# baseboard.net
KiCad netlist of a schematic drawn in EAGLE
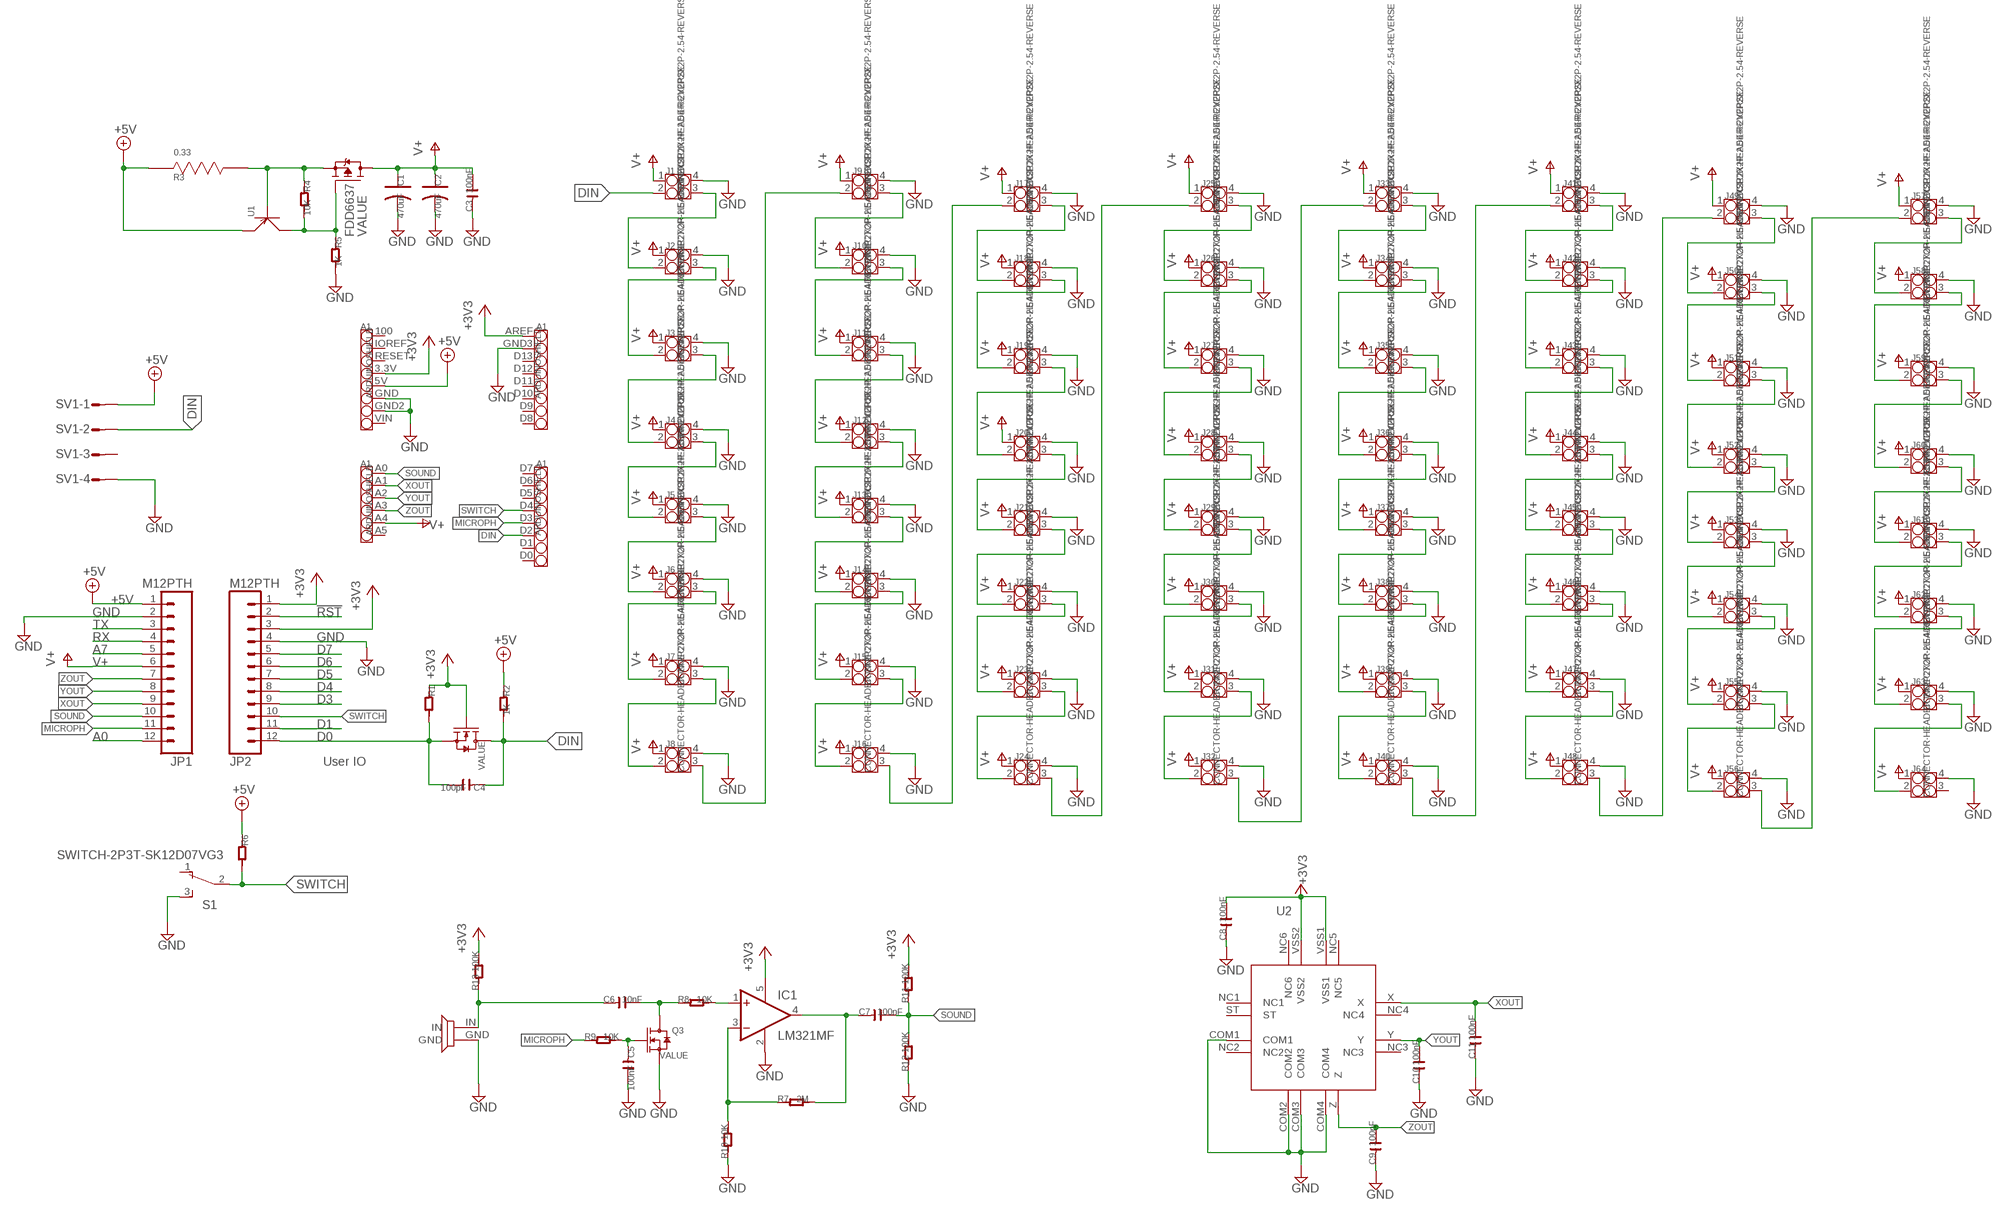
[diagram p0: schematic, sheet 1]

(export (version "E")
  (design (tool "Eeschema 10.0.6"))
  (components
    (comp (ref "2N7002")
      (value "MOSFET-N-044020001")
      (footprint "eagle-import:SOT23")
      (libsource (lib "eagle-import") (part "MOSFET-N-044020001"))
    )
    (comp (ref "A1")
      (value "ARDUINOSHIELD")
      (footprint "eagle-import:ARDUINOSHIELD")
      (libsource (lib "eagle-import") (part "ARDUINOSHIELD"))
    )
    (comp (ref "C1")
      (value "470uF")
      (footprint "eagle-import:CAPACITOR-E5-8.5")
      (libsource (lib "eagle-import") (part "C-POLARCAPACITOR-E5-8.5"))
    )
    (comp (ref "C2")
      (value "470uF")
      (footprint "eagle-import:CAPACITOR-E5-8.5")
      (libsource (lib "eagle-import") (part "C-POLARCAPACITOR-E5-8.5"))
    )
    (comp (ref "C3")
      (value "100nF")
      (footprint "eagle-import:C0603")
      (libsource (lib "eagle-import") (part "C-0603"))
    )
    (comp (ref "C4")
      (value "100pF")
      (footprint "eagle-import:C0603")
      (libsource (lib "eagle-import") (part "C-0603"))
    )
    (comp (ref "C5")
      (value "100nF")
      (footprint "eagle-import:C0603")
      (libsource (lib "eagle-import") (part "C-0603"))
    )
    (comp (ref "C6")
      (value "10nF")
      (footprint "eagle-import:C0603")
      (libsource (lib "eagle-import") (part "C-0603"))
    )
    (comp (ref "C7")
      (value "100nF")
      (footprint "eagle-import:C0603")
      (libsource (lib "eagle-import") (part "C-0603"))
    )
    (comp (ref "C8")
      (value "100nF")
      (footprint "eagle-import:C0603")
      (libsource (lib "eagle-import") (part "C-0603"))
    )
    (comp (ref "C9")
      (value "100nF")
      (footprint "eagle-import:C0603")
      (libsource (lib "eagle-import") (part "C-0603"))
    )
    (comp (ref "C10")
      (value "100nF")
      (footprint "eagle-import:C0603")
      (libsource (lib "eagle-import") (part "C-0603"))
    )
    (comp (ref "C11")
      (value "100nF")
      (footprint "eagle-import:C0603")
      (libsource (lib "eagle-import") (part "C-0603"))
    )
    (comp (ref "FDD6637")
      (value "FDD4141TO252")
      (footprint "eagle-import:TO252")
      (libsource (lib "eagle-import") (part "FDD4141TO252"))
    )
    (comp (ref "IC1")
      (value "LM321MF")
      (footprint "eagle-import:SOT23-5")
      (libsource (lib "eagle-import") (part "LM321?MF"))
    )
    (comp (ref "J1")
      (value "CONNECTOR-HEADER-2X2P2X2P-2.54-REVERSE")
      (footprint "eagle-import:2X2P-2.54-REVERSE")
      (libsource (lib "eagle-import") (part "CONNECTOR-HEADER-2X2P2X2P-2.54-REVERSE"))
    )
    (comp (ref "J2")
      (value "CONNECTOR-HEADER-2X2P2X2P-2.54-REVERSE")
      (footprint "eagle-import:2X2P-2.54-REVERSE")
      (libsource (lib "eagle-import") (part "CONNECTOR-HEADER-2X2P2X2P-2.54-REVERSE"))
    )
    (comp (ref "J3")
      (value "CONNECTOR-HEADER-2X2P2X2P-2.54-REVERSE")
      (footprint "eagle-import:2X2P-2.54-REVERSE")
      (libsource (lib "eagle-import") (part "CONNECTOR-HEADER-2X2P2X2P-2.54-REVERSE"))
    )
    (comp (ref "J4")
      (value "CONNECTOR-HEADER-2X2P2X2P-2.54-REVERSE")
      (footprint "eagle-import:2X2P-2.54-REVERSE")
      (libsource (lib "eagle-import") (part "CONNECTOR-HEADER-2X2P2X2P-2.54-REVERSE"))
    )
    (comp (ref "J5")
      (value "CONNECTOR-HEADER-2X2P2X2P-2.54-REVERSE")
      (footprint "eagle-import:2X2P-2.54-REVERSE")
      (libsource (lib "eagle-import") (part "CONNECTOR-HEADER-2X2P2X2P-2.54-REVERSE"))
    )
    (comp (ref "J6")
      (value "CONNECTOR-HEADER-2X2P2X2P-2.54-REVERSE")
      (footprint "eagle-import:2X2P-2.54-REVERSE")
      (libsource (lib "eagle-import") (part "CONNECTOR-HEADER-2X2P2X2P-2.54-REVERSE"))
    )
    (comp (ref "J7")
      (value "CONNECTOR-HEADER-2X2P2X2P-2.54-REVERSE")
      (footprint "eagle-import:2X2P-2.54-REVERSE")
      (libsource (lib "eagle-import") (part "CONNECTOR-HEADER-2X2P2X2P-2.54-REVERSE"))
    )
    (comp (ref "J8")
      (value "CONNECTOR-HEADER-2X2P2X2P-2.54-REVERSE")
      (footprint "eagle-import:2X2P-2.54-REVERSE")
      (libsource (lib "eagle-import") (part "CONNECTOR-HEADER-2X2P2X2P-2.54-REVERSE"))
    )
    (comp (ref "J9")
      (value "CONNECTOR-HEADER-2X2P2X2P-2.54-REVERSE")
      (footprint "eagle-import:2X2P-2.54-REVERSE")
      (libsource (lib "eagle-import") (part "CONNECTOR-HEADER-2X2P2X2P-2.54-REVERSE"))
    )
    (comp (ref "J10")
      (value "CONNECTOR-HEADER-2X2P2X2P-2.54-REVERSE")
      (footprint "eagle-import:2X2P-2.54-REVERSE")
      (libsource (lib "eagle-import") (part "CONNECTOR-HEADER-2X2P2X2P-2.54-REVERSE"))
    )
    (comp (ref "J11")
      (value "CONNECTOR-HEADER-2X2P2X2P-2.54-REVERSE")
      (footprint "eagle-import:2X2P-2.54-REVERSE")
      (libsource (lib "eagle-import") (part "CONNECTOR-HEADER-2X2P2X2P-2.54-REVERSE"))
    )
    (comp (ref "J12")
      (value "CONNECTOR-HEADER-2X2P2X2P-2.54-REVERSE")
      (footprint "eagle-import:2X2P-2.54-REVERSE")
      (libsource (lib "eagle-import") (part "CONNECTOR-HEADER-2X2P2X2P-2.54-REVERSE"))
    )
    (comp (ref "J13")
      (value "CONNECTOR-HEADER-2X2P2X2P-2.54-REVERSE")
      (footprint "eagle-import:2X2P-2.54-REVERSE")
      (libsource (lib "eagle-import") (part "CONNECTOR-HEADER-2X2P2X2P-2.54-REVERSE"))
    )
    (comp (ref "J14")
      (value "CONNECTOR-HEADER-2X2P2X2P-2.54-REVERSE")
      (footprint "eagle-import:2X2P-2.54-REVERSE")
      (libsource (lib "eagle-import") (part "CONNECTOR-HEADER-2X2P2X2P-2.54-REVERSE"))
    )
    (comp (ref "J15")
      (value "CONNECTOR-HEADER-2X2P2X2P-2.54-REVERSE")
      (footprint "eagle-import:2X2P-2.54-REVERSE")
      (libsource (lib "eagle-import") (part "CONNECTOR-HEADER-2X2P2X2P-2.54-REVERSE"))
    )
    (comp (ref "J16")
      (value "CONNECTOR-HEADER-2X2P2X2P-2.54-REVERSE")
      (footprint "eagle-import:2X2P-2.54-REVERSE")
      (libsource (lib "eagle-import") (part "CONNECTOR-HEADER-2X2P2X2P-2.54-REVERSE"))
    )
    (comp (ref "J17")
      (value "CONNECTOR-HEADER-2X2P2X2P-2.54-REVERSE")
      (footprint "eagle-import:2X2P-2.54-REVERSE")
      (libsource (lib "eagle-import") (part "CONNECTOR-HEADER-2X2P2X2P-2.54-REVERSE"))
    )
    (comp (ref "J18")
      (value "CONNECTOR-HEADER-2X2P2X2P-2.54-REVERSE")
      (footprint "eagle-import:2X2P-2.54-REVERSE")
      (libsource (lib "eagle-import") (part "CONNECTOR-HEADER-2X2P2X2P-2.54-REVERSE"))
    )
    (comp (ref "J19")
      (value "CONNECTOR-HEADER-2X2P2X2P-2.54-REVERSE")
      (footprint "eagle-import:2X2P-2.54-REVERSE")
      (libsource (lib "eagle-import") (part "CONNECTOR-HEADER-2X2P2X2P-2.54-REVERSE"))
    )
    (comp (ref "J20")
      (value "CONNECTOR-HEADER-2X2P2X2P-2.54-REVERSE")
      (footprint "eagle-import:2X2P-2.54-REVERSE")
      (libsource (lib "eagle-import") (part "CONNECTOR-HEADER-2X2P2X2P-2.54-REVERSE"))
    )
    (comp (ref "J21")
      (value "CONNECTOR-HEADER-2X2P2X2P-2.54-REVERSE")
      (footprint "eagle-import:2X2P-2.54-REVERSE")
      (libsource (lib "eagle-import") (part "CONNECTOR-HEADER-2X2P2X2P-2.54-REVERSE"))
    )
    (comp (ref "J22")
      (value "CONNECTOR-HEADER-2X2P2X2P-2.54-REVERSE")
      (footprint "eagle-import:2X2P-2.54-REVERSE")
      (libsource (lib "eagle-import") (part "CONNECTOR-HEADER-2X2P2X2P-2.54-REVERSE"))
    )
    (comp (ref "J23")
      (value "CONNECTOR-HEADER-2X2P2X2P-2.54-REVERSE")
      (footprint "eagle-import:2X2P-2.54-REVERSE")
      (libsource (lib "eagle-import") (part "CONNECTOR-HEADER-2X2P2X2P-2.54-REVERSE"))
    )
    (comp (ref "J24")
      (value "CONNECTOR-HEADER-2X2P2X2P-2.54-REVERSE")
      (footprint "eagle-import:2X2P-2.54-REVERSE")
      (libsource (lib "eagle-import") (part "CONNECTOR-HEADER-2X2P2X2P-2.54-REVERSE"))
    )
    (comp (ref "J25")
      (value "CONNECTOR-HEADER-2X2P2X2P-2.54-REVERSE")
      (footprint "eagle-import:2X2P-2.54-REVERSE")
      (libsource (lib "eagle-import") (part "CONNECTOR-HEADER-2X2P2X2P-2.54-REVERSE"))
    )
    (comp (ref "J26")
      (value "CONNECTOR-HEADER-2X2P2X2P-2.54-REVERSE")
      (footprint "eagle-import:2X2P-2.54-REVERSE")
      (libsource (lib "eagle-import") (part "CONNECTOR-HEADER-2X2P2X2P-2.54-REVERSE"))
    )
    (comp (ref "J27")
      (value "CONNECTOR-HEADER-2X2P2X2P-2.54-REVERSE")
      (footprint "eagle-import:2X2P-2.54-REVERSE")
      (libsource (lib "eagle-import") (part "CONNECTOR-HEADER-2X2P2X2P-2.54-REVERSE"))
    )
    (comp (ref "J28")
      (value "CONNECTOR-HEADER-2X2P2X2P-2.54-REVERSE")
      (footprint "eagle-import:2X2P-2.54-REVERSE")
      (libsource (lib "eagle-import") (part "CONNECTOR-HEADER-2X2P2X2P-2.54-REVERSE"))
    )
    (comp (ref "J29")
      (value "CONNECTOR-HEADER-2X2P2X2P-2.54-REVERSE")
      (footprint "eagle-import:2X2P-2.54-REVERSE")
      (libsource (lib "eagle-import") (part "CONNECTOR-HEADER-2X2P2X2P-2.54-REVERSE"))
    )
    (comp (ref "J30")
      (value "CONNECTOR-HEADER-2X2P2X2P-2.54-REVERSE")
      (footprint "eagle-import:2X2P-2.54-REVERSE")
      (libsource (lib "eagle-import") (part "CONNECTOR-HEADER-2X2P2X2P-2.54-REVERSE"))
    )
    (comp (ref "J31")
      (value "CONNECTOR-HEADER-2X2P2X2P-2.54-REVERSE")
      (footprint "eagle-import:2X2P-2.54-REVERSE")
      (libsource (lib "eagle-import") (part "CONNECTOR-HEADER-2X2P2X2P-2.54-REVERSE"))
    )
    (comp (ref "J32")
      (value "CONNECTOR-HEADER-2X2P2X2P-2.54-REVERSE")
      (footprint "eagle-import:2X2P-2.54-REVERSE")
      (libsource (lib "eagle-import") (part "CONNECTOR-HEADER-2X2P2X2P-2.54-REVERSE"))
    )
    (comp (ref "J33")
      (value "CONNECTOR-HEADER-2X2P2X2P-2.54-REVERSE")
      (footprint "eagle-import:2X2P-2.54-REVERSE")
      (libsource (lib "eagle-import") (part "CONNECTOR-HEADER-2X2P2X2P-2.54-REVERSE"))
    )
    (comp (ref "J34")
      (value "CONNECTOR-HEADER-2X2P2X2P-2.54-REVERSE")
      (footprint "eagle-import:2X2P-2.54-REVERSE")
      (libsource (lib "eagle-import") (part "CONNECTOR-HEADER-2X2P2X2P-2.54-REVERSE"))
    )
    (comp (ref "J35")
      (value "CONNECTOR-HEADER-2X2P2X2P-2.54-REVERSE")
      (footprint "eagle-import:2X2P-2.54-REVERSE")
      (libsource (lib "eagle-import") (part "CONNECTOR-HEADER-2X2P2X2P-2.54-REVERSE"))
    )
    (comp (ref "J36")
      (value "CONNECTOR-HEADER-2X2P2X2P-2.54-REVERSE")
      (footprint "eagle-import:2X2P-2.54-REVERSE")
      (libsource (lib "eagle-import") (part "CONNECTOR-HEADER-2X2P2X2P-2.54-REVERSE"))
    )
    (comp (ref "J37")
      (value "CONNECTOR-HEADER-2X2P2X2P-2.54-REVERSE")
      (footprint "eagle-import:2X2P-2.54-REVERSE")
      (libsource (lib "eagle-import") (part "CONNECTOR-HEADER-2X2P2X2P-2.54-REVERSE"))
    )
    (comp (ref "J38")
      (value "CONNECTOR-HEADER-2X2P2X2P-2.54-REVERSE")
      (footprint "eagle-import:2X2P-2.54-REVERSE")
      (libsource (lib "eagle-import") (part "CONNECTOR-HEADER-2X2P2X2P-2.54-REVERSE"))
    )
    (comp (ref "J39")
      (value "CONNECTOR-HEADER-2X2P2X2P-2.54-REVERSE")
      (footprint "eagle-import:2X2P-2.54-REVERSE")
      (libsource (lib "eagle-import") (part "CONNECTOR-HEADER-2X2P2X2P-2.54-REVERSE"))
    )
    (comp (ref "J40")
      (value "CONNECTOR-HEADER-2X2P2X2P-2.54-REVERSE")
      (footprint "eagle-import:2X2P-2.54-REVERSE")
      (libsource (lib "eagle-import") (part "CONNECTOR-HEADER-2X2P2X2P-2.54-REVERSE"))
    )
    (comp (ref "J41")
      (value "CONNECTOR-HEADER-2X2P2X2P-2.54-REVERSE")
      (footprint "eagle-import:2X2P-2.54-REVERSE")
      (libsource (lib "eagle-import") (part "CONNECTOR-HEADER-2X2P2X2P-2.54-REVERSE"))
    )
    (comp (ref "J42")
      (value "CONNECTOR-HEADER-2X2P2X2P-2.54-REVERSE")
      (footprint "eagle-import:2X2P-2.54-REVERSE")
      (libsource (lib "eagle-import") (part "CONNECTOR-HEADER-2X2P2X2P-2.54-REVERSE"))
    )
    (comp (ref "J43")
      (value "CONNECTOR-HEADER-2X2P2X2P-2.54-REVERSE")
      (footprint "eagle-import:2X2P-2.54-REVERSE")
      (libsource (lib "eagle-import") (part "CONNECTOR-HEADER-2X2P2X2P-2.54-REVERSE"))
    )
    (comp (ref "J44")
      (value "CONNECTOR-HEADER-2X2P2X2P-2.54-REVERSE")
      (footprint "eagle-import:2X2P-2.54-REVERSE")
      (libsource (lib "eagle-import") (part "CONNECTOR-HEADER-2X2P2X2P-2.54-REVERSE"))
    )
    (comp (ref "J45")
      (value "CONNECTOR-HEADER-2X2P2X2P-2.54-REVERSE")
      (footprint "eagle-import:2X2P-2.54-REVERSE")
      (libsource (lib "eagle-import") (part "CONNECTOR-HEADER-2X2P2X2P-2.54-REVERSE"))
    )
    (comp (ref "J46")
      (value "CONNECTOR-HEADER-2X2P2X2P-2.54-REVERSE")
      (footprint "eagle-import:2X2P-2.54-REVERSE")
      (libsource (lib "eagle-import") (part "CONNECTOR-HEADER-2X2P2X2P-2.54-REVERSE"))
    )
    (comp (ref "J47")
      (value "CONNECTOR-HEADER-2X2P2X2P-2.54-REVERSE")
      (footprint "eagle-import:2X2P-2.54-REVERSE")
      (libsource (lib "eagle-import") (part "CONNECTOR-HEADER-2X2P2X2P-2.54-REVERSE"))
    )
    (comp (ref "J48")
      (value "CONNECTOR-HEADER-2X2P2X2P-2.54-REVERSE")
      (footprint "eagle-import:2X2P-2.54-REVERSE")
      (libsource (lib "eagle-import") (part "CONNECTOR-HEADER-2X2P2X2P-2.54-REVERSE"))
    )
    (comp (ref "J49")
      (value "CONNECTOR-HEADER-2X2P2X2P-2.54-REVERSE")
      (footprint "eagle-import:2X2P-2.54-REVERSE")
      (libsource (lib "eagle-import") (part "CONNECTOR-HEADER-2X2P2X2P-2.54-REVERSE"))
    )
    (comp (ref "J50")
      (value "CONNECTOR-HEADER-2X2P2X2P-2.54-REVERSE")
      (footprint "eagle-import:2X2P-2.54-REVERSE")
      (libsource (lib "eagle-import") (part "CONNECTOR-HEADER-2X2P2X2P-2.54-REVERSE"))
    )
    (comp (ref "J51")
      (value "CONNECTOR-HEADER-2X2P2X2P-2.54-REVERSE")
      (footprint "eagle-import:2X2P-2.54-REVERSE")
      (libsource (lib "eagle-import") (part "CONNECTOR-HEADER-2X2P2X2P-2.54-REVERSE"))
    )
    (comp (ref "J52")
      (value "CONNECTOR-HEADER-2X2P2X2P-2.54-REVERSE")
      (footprint "eagle-import:2X2P-2.54-REVERSE")
      (libsource (lib "eagle-import") (part "CONNECTOR-HEADER-2X2P2X2P-2.54-REVERSE"))
    )
    (comp (ref "J53")
      (value "CONNECTOR-HEADER-2X2P2X2P-2.54-REVERSE")
      (footprint "eagle-import:2X2P-2.54-REVERSE")
      (libsource (lib "eagle-import") (part "CONNECTOR-HEADER-2X2P2X2P-2.54-REVERSE"))
    )
    (comp (ref "J54")
      (value "CONNECTOR-HEADER-2X2P2X2P-2.54-REVERSE")
      (footprint "eagle-import:2X2P-2.54-REVERSE")
      (libsource (lib "eagle-import") (part "CONNECTOR-HEADER-2X2P2X2P-2.54-REVERSE"))
    )
    (comp (ref "J55")
      (value "CONNECTOR-HEADER-2X2P2X2P-2.54-REVERSE")
      (footprint "eagle-import:2X2P-2.54-REVERSE")
      (libsource (lib "eagle-import") (part "CONNECTOR-HEADER-2X2P2X2P-2.54-REVERSE"))
    )
    (comp (ref "J56")
      (value "CONNECTOR-HEADER-2X2P2X2P-2.54-REVERSE")
      (footprint "eagle-import:2X2P-2.54-REVERSE")
      (libsource (lib "eagle-import") (part "CONNECTOR-HEADER-2X2P2X2P-2.54-REVERSE"))
    )
    (comp (ref "J57")
      (value "CONNECTOR-HEADER-2X2P2X2P-2.54-REVERSE")
      (footprint "eagle-import:2X2P-2.54-REVERSE")
      (libsource (lib "eagle-import") (part "CONNECTOR-HEADER-2X2P2X2P-2.54-REVERSE"))
    )
    (comp (ref "J58")
      (value "CONNECTOR-HEADER-2X2P2X2P-2.54-REVERSE")
      (footprint "eagle-import:2X2P-2.54-REVERSE")
      (libsource (lib "eagle-import") (part "CONNECTOR-HEADER-2X2P2X2P-2.54-REVERSE"))
    )
    (comp (ref "J59")
      (value "CONNECTOR-HEADER-2X2P2X2P-2.54-REVERSE")
      (footprint "eagle-import:2X2P-2.54-REVERSE")
      (libsource (lib "eagle-import") (part "CONNECTOR-HEADER-2X2P2X2P-2.54-REVERSE"))
    )
    (comp (ref "J60")
      (value "CONNECTOR-HEADER-2X2P2X2P-2.54-REVERSE")
      (footprint "eagle-import:2X2P-2.54-REVERSE")
      (libsource (lib "eagle-import") (part "CONNECTOR-HEADER-2X2P2X2P-2.54-REVERSE"))
    )
    (comp (ref "J61")
      (value "CONNECTOR-HEADER-2X2P2X2P-2.54-REVERSE")
      (footprint "eagle-import:2X2P-2.54-REVERSE")
      (libsource (lib "eagle-import") (part "CONNECTOR-HEADER-2X2P2X2P-2.54-REVERSE"))
    )
    (comp (ref "J62")
      (value "CONNECTOR-HEADER-2X2P2X2P-2.54-REVERSE")
      (footprint "eagle-import:2X2P-2.54-REVERSE")
      (libsource (lib "eagle-import") (part "CONNECTOR-HEADER-2X2P2X2P-2.54-REVERSE"))
    )
    (comp (ref "J63")
      (value "CONNECTOR-HEADER-2X2P2X2P-2.54-REVERSE")
      (footprint "eagle-import:2X2P-2.54-REVERSE")
      (libsource (lib "eagle-import") (part "CONNECTOR-HEADER-2X2P2X2P-2.54-REVERSE"))
    )
    (comp (ref "J64")
      (value "CONNECTOR-HEADER-2X2P2X2P-2.54-REVERSE")
      (footprint "eagle-import:2X2P-2.54-REVERSE")
      (libsource (lib "eagle-import") (part "CONNECTOR-HEADER-2X2P2X2P-2.54-REVERSE"))
    )
    (comp (ref "JP1")
      (value "M12PTH")
      (footprint "eagle-import:1X12-SMALL-PADS")
      (libsource (lib "eagle-import") (part "M12PTH"))
    )
    (comp (ref "JP2")
      (value "M12PTH")
      (footprint "eagle-import:1X12-SMALL-PADS")
      (libsource (lib "eagle-import") (part "M12PTH"))
    )
    (comp (ref "Q3")
      (value "MOSFET-N-044020001")
      (footprint "eagle-import:SOT23")
      (libsource (lib "eagle-import") (part "MOSFET-N-044020001"))
    )
    (comp (ref "R1")
      (value "R-0603")
      (footprint "eagle-import:R0603")
      (libsource (lib "eagle-import") (part "R-0603"))
    )
    (comp (ref "R2")
      (value "1K")
      (footprint "eagle-import:R0603")
      (libsource (lib "eagle-import") (part "R-0603"))
    )
    (comp (ref "R3")
      (value "0.33")
      (footprint "eagle-import:RESISTOR-3W-20MM")
      (libsource (lib "eagle-import") (part "RESISTOR-3W-20MM"))
    )
    (comp (ref "R4")
      (value "10K")
      (footprint "eagle-import:R0603")
      (libsource (lib "eagle-import") (part "R-0603"))
    )
    (comp (ref "R5")
      (value "1K")
      (footprint "eagle-import:R0603")
      (libsource (lib "eagle-import") (part "R-0603"))
    )
    (comp (ref "R6")
      (value "R-0603")
      (footprint "eagle-import:R0603")
      (libsource (lib "eagle-import") (part "R-0603"))
    )
    (comp (ref "R7")
      (value "2M")
      (footprint "eagle-import:R0603")
      (libsource (lib "eagle-import") (part "R-0603"))
    )
    (comp (ref "R8")
      (value "10K")
      (footprint "eagle-import:R0603")
      (libsource (lib "eagle-import") (part "R-0603"))
    )
    (comp (ref "R9")
      (value "10K")
      (footprint "eagle-import:R0603")
      (libsource (lib "eagle-import") (part "R-0603"))
    )
    (comp (ref "R10")
      (value "10K")
      (footprint "eagle-import:R0603")
      (libsource (lib "eagle-import") (part "R-0603"))
    )
    (comp (ref "R11")
      (value "100K")
      (footprint "eagle-import:R0603")
      (libsource (lib "eagle-import") (part "R-0603"))
    )
    (comp (ref "R12")
      (value "100K")
      (footprint "eagle-import:R0603")
      (libsource (lib "eagle-import") (part "R-0603"))
    )
    (comp (ref "R13")
      (value "100K")
      (footprint "eagle-import:R0603")
      (libsource (lib "eagle-import") (part "R-0603"))
    )
    (comp (ref "S1")
      (value "SWITCH-2P3T-SK12D07VG3")
      (footprint "eagle-import:SWITCH-2P3T-SK12D07VG3")
      (libsource (lib "eagle-import") (part "SWITCH-2P3T-SK12D07VG3"))
    )
    (comp (ref "SV1")
      (value "S04P")
      (footprint "eagle-import:S04P")
      (libsource (lib "eagle-import") (part "S04P"))
    )
    (comp (ref "U$1")
      (value "MICROPHONE")
      (footprint "eagle-import:MICROPHONE")
      (libsource (lib "eagle-import") (part "MICROPHONE"))
    )
    (comp (ref "U1")
      (value "TRANSISTOR-PNP-041003001")
      (footprint "eagle-import:SOT23")
      (libsource (lib "eagle-import") (part "TRANSISTOR-PNP-041003001"))
    )
    (comp (ref "U2")
      (value "ADXL335")
      (footprint "eagle-import:ADXL335")
      (libsource (lib "eagle-import") (part "ADXL335"))
    )
  )
  (nets
    (net (code "1") (name "+3V3") (class "Default")
      (node (ref "2N7002") (pin "1") (pinfunction "G_1") (pintype "passive"))
      (node (ref "A1") (pin "3.3V") (pinfunction "3.3V_3.3V") (pintype "bidirectional"))
      (node (ref "A1") (pin "AREF") (pinfunction "AREF_AREF") (pintype "bidirectional"))
      (node (ref "C8") (pin "2") (pinfunction "2_2") (pintype "bidirectional"))
      (node (ref "IC1") (pin "5") (pinfunction "V+_5") (pintype "power_in"))
      (node (ref "JP2") (pin "1") (pinfunction "1_1") (pintype "passive"))
      (node (ref "JP2") (pin "3") (pinfunction "3_3") (pintype "passive"))
      (node (ref "R1") (pin "1") (pinfunction "1_1") (pintype "bidirectional"))
      (node (ref "R11") (pin "2") (pinfunction "2_2") (pintype "bidirectional"))
      (node (ref "R13") (pin "2") (pinfunction "2_2") (pintype "bidirectional"))
      (node (ref "U2") (pin "VSS1") (pinfunction "VSS1_VSS1") (pintype "bidirectional"))
      (node (ref "U2") (pin "VSS2") (pinfunction "VSS2_VSS2") (pintype "bidirectional"))
    )
    (net (code "2") (name "+5V") (class "Default")
      (node (ref "A1") (pin "5V") (pinfunction "5V_5V") (pintype "bidirectional"))
      (node (ref "JP1") (pin "1") (pinfunction "1_1") (pintype "passive"))
      (node (ref "R2") (pin "1") (pinfunction "1_1") (pintype "bidirectional"))
      (node (ref "R3") (pin "1") (pinfunction "1_1") (pintype "bidirectional"))
      (node (ref "R6") (pin "1") (pinfunction "1_1") (pintype "bidirectional"))
      (node (ref "SV1") (pin "1") (pinfunction "S_1") (pintype "passive"))
      (node (ref "U1") (pin "2") (pinfunction "E_2") (pintype "passive"))
    )
    (net (code "3") (name "/A0") (class "Default")
      (node (ref "JP1") (pin "12") (pinfunction "12_12") (pintype "passive"))
    )
    (net (code "4") (name "/A7") (class "Default")
      (node (ref "JP1") (pin "5") (pinfunction "5_5") (pintype "passive"))
    )
    (net (code "5") (name "/D0") (class "Default")
      (node (ref "2N7002") (pin "2") (pinfunction "S_2") (pintype "passive"))
      (node (ref "C4") (pin "2") (pinfunction "2_2") (pintype "bidirectional"))
      (node (ref "JP2") (pin "12") (pinfunction "12_12") (pintype "passive"))
      (node (ref "R1") (pin "2") (pinfunction "2_2") (pintype "bidirectional"))
    )
    (net (code "6") (name "/D1") (class "Default")
      (node (ref "JP2") (pin "11") (pinfunction "11_11") (pintype "passive"))
    )
    (net (code "7") (name "/D3") (class "Default")
      (node (ref "JP2") (pin "9") (pinfunction "9_9") (pintype "passive"))
    )
    (net (code "8") (name "/D4") (class "Default")
      (node (ref "JP2") (pin "8") (pinfunction "8_8") (pintype "passive"))
    )
    (net (code "9") (name "/D5") (class "Default")
      (node (ref "JP2") (pin "7") (pinfunction "7_7") (pintype "passive"))
    )
    (net (code "10") (name "/D6") (class "Default")
      (node (ref "JP2") (pin "6") (pinfunction "6_6") (pintype "passive"))
    )
    (net (code "11") (name "/D7") (class "Default")
      (node (ref "JP2") (pin "5") (pinfunction "5_5") (pintype "passive"))
    )
    (net (code "12") (name "/RX") (class "Default")
      (node (ref "JP1") (pin "4") (pinfunction "4_4") (pintype "passive"))
    )
    (net (code "13") (name "/TX") (class "Default")
      (node (ref "JP1") (pin "3") (pinfunction "3_3") (pintype "passive"))
    )
    (net (code "14") (name "/~{RST}") (class "Default")
      (node (ref "JP2") (pin "2") (pinfunction "2_2") (pintype "passive"))
    )
    (net (code "15") (name "DIN") (class "Default")
      (node (ref "2N7002") (pin "3") (pinfunction "D_3") (pintype "passive"))
      (node (ref "A1") (pin "D2") (pinfunction "D2_D2") (pintype "bidirectional"))
      (node (ref "C4") (pin "1") (pinfunction "1_1") (pintype "bidirectional"))
      (node (ref "J1") (pin "2") (pinfunction "2_2") (pintype "bidirectional"))
      (node (ref "R2") (pin "2") (pinfunction "2_2") (pintype "bidirectional"))
      (node (ref "SV1") (pin "2") (pinfunction "S_2") (pintype "passive"))
    )
    (net (code "16") (name "GND") (class "Default")
      (node (ref "A1") (pin "GND") (pinfunction "GND_GND") (pintype "bidirectional"))
      (node (ref "A1") (pin "GND2") (pinfunction "GND2_GND2") (pintype "bidirectional"))
      (node (ref "A1") (pin "GND3") (pinfunction "GND3_GND3") (pintype "bidirectional"))
      (node (ref "C1") (pin "-") (pinfunction "2_-") (pintype "bidirectional"))
      (node (ref "C10") (pin "1") (pinfunction "1_1") (pintype "bidirectional"))
      (node (ref "C11") (pin "1") (pinfunction "1_1") (pintype "bidirectional"))
      (node (ref "C2") (pin "-") (pinfunction "2_-") (pintype "bidirectional"))
      (node (ref "C3") (pin "1") (pinfunction "1_1") (pintype "bidirectional"))
      (node (ref "C5") (pin "2") (pinfunction "2_2") (pintype "bidirectional"))
      (node (ref "C8") (pin "1") (pinfunction "1_1") (pintype "bidirectional"))
      (node (ref "C9") (pin "1") (pinfunction "1_1") (pintype "bidirectional"))
      (node (ref "IC1") (pin "2") (pinfunction "V-_2") (pintype "power_in"))
      (node (ref "J1") (pin "4") (pinfunction "4_4") (pintype "bidirectional"))
      (node (ref "J10") (pin "4") (pinfunction "4_4") (pintype "bidirectional"))
      (node (ref "J11") (pin "4") (pinfunction "4_4") (pintype "bidirectional"))
      (node (ref "J12") (pin "4") (pinfunction "4_4") (pintype "bidirectional"))
      (node (ref "J13") (pin "4") (pinfunction "4_4") (pintype "bidirectional"))
      (node (ref "J14") (pin "4") (pinfunction "4_4") (pintype "bidirectional"))
      (node (ref "J15") (pin "4") (pinfunction "4_4") (pintype "bidirectional"))
      (node (ref "J16") (pin "4") (pinfunction "4_4") (pintype "bidirectional"))
      (node (ref "J17") (pin "4") (pinfunction "4_4") (pintype "bidirectional"))
      (node (ref "J18") (pin "4") (pinfunction "4_4") (pintype "bidirectional"))
      (node (ref "J19") (pin "4") (pinfunction "4_4") (pintype "bidirectional"))
      (node (ref "J2") (pin "4") (pinfunction "4_4") (pintype "bidirectional"))
      (node (ref "J20") (pin "4") (pinfunction "4_4") (pintype "bidirectional"))
      (node (ref "J21") (pin "4") (pinfunction "4_4") (pintype "bidirectional"))
      (node (ref "J22") (pin "4") (pinfunction "4_4") (pintype "bidirectional"))
      (node (ref "J23") (pin "4") (pinfunction "4_4") (pintype "bidirectional"))
      (node (ref "J24") (pin "4") (pinfunction "4_4") (pintype "bidirectional"))
      (node (ref "J25") (pin "4") (pinfunction "4_4") (pintype "bidirectional"))
      (node (ref "J26") (pin "4") (pinfunction "4_4") (pintype "bidirectional"))
      (node (ref "J27") (pin "4") (pinfunction "4_4") (pintype "bidirectional"))
      (node (ref "J28") (pin "4") (pinfunction "4_4") (pintype "bidirectional"))
      (node (ref "J29") (pin "4") (pinfunction "4_4") (pintype "bidirectional"))
      (node (ref "J3") (pin "4") (pinfunction "4_4") (pintype "bidirectional"))
      (node (ref "J30") (pin "4") (pinfunction "4_4") (pintype "bidirectional"))
      (node (ref "J31") (pin "4") (pinfunction "4_4") (pintype "bidirectional"))
      (node (ref "J32") (pin "4") (pinfunction "4_4") (pintype "bidirectional"))
      (node (ref "J33") (pin "4") (pinfunction "4_4") (pintype "bidirectional"))
      (node (ref "J34") (pin "4") (pinfunction "4_4") (pintype "bidirectional"))
      (node (ref "J35") (pin "4") (pinfunction "4_4") (pintype "bidirectional"))
      (node (ref "J36") (pin "4") (pinfunction "4_4") (pintype "bidirectional"))
      (node (ref "J37") (pin "4") (pinfunction "4_4") (pintype "bidirectional"))
      (node (ref "J38") (pin "4") (pinfunction "4_4") (pintype "bidirectional"))
      (node (ref "J39") (pin "4") (pinfunction "4_4") (pintype "bidirectional"))
      (node (ref "J4") (pin "4") (pinfunction "4_4") (pintype "bidirectional"))
      (node (ref "J40") (pin "4") (pinfunction "4_4") (pintype "bidirectional"))
      (node (ref "J41") (pin "4") (pinfunction "4_4") (pintype "bidirectional"))
      (node (ref "J42") (pin "4") (pinfunction "4_4") (pintype "bidirectional"))
      (node (ref "J43") (pin "4") (pinfunction "4_4") (pintype "bidirectional"))
      (node (ref "J44") (pin "4") (pinfunction "4_4") (pintype "bidirectional"))
      (node (ref "J45") (pin "4") (pinfunction "4_4") (pintype "bidirectional"))
      (node (ref "J46") (pin "4") (pinfunction "4_4") (pintype "bidirectional"))
      (node (ref "J47") (pin "4") (pinfunction "4_4") (pintype "bidirectional"))
      (node (ref "J48") (pin "4") (pinfunction "4_4") (pintype "bidirectional"))
      (node (ref "J49") (pin "4") (pinfunction "4_4") (pintype "bidirectional"))
      (node (ref "J5") (pin "4") (pinfunction "4_4") (pintype "bidirectional"))
      (node (ref "J50") (pin "4") (pinfunction "4_4") (pintype "bidirectional"))
      (node (ref "J51") (pin "4") (pinfunction "4_4") (pintype "bidirectional"))
      (node (ref "J52") (pin "4") (pinfunction "4_4") (pintype "bidirectional"))
      (node (ref "J53") (pin "4") (pinfunction "4_4") (pintype "bidirectional"))
      (node (ref "J54") (pin "4") (pinfunction "4_4") (pintype "bidirectional"))
      (node (ref "J55") (pin "4") (pinfunction "4_4") (pintype "bidirectional"))
      (node (ref "J56") (pin "4") (pinfunction "4_4") (pintype "bidirectional"))
      (node (ref "J57") (pin "4") (pinfunction "4_4") (pintype "bidirectional"))
      (node (ref "J58") (pin "4") (pinfunction "4_4") (pintype "bidirectional"))
      (node (ref "J59") (pin "4") (pinfunction "4_4") (pintype "bidirectional"))
      (node (ref "J6") (pin "4") (pinfunction "4_4") (pintype "bidirectional"))
      (node (ref "J60") (pin "4") (pinfunction "4_4") (pintype "bidirectional"))
      (node (ref "J61") (pin "4") (pinfunction "4_4") (pintype "bidirectional"))
      (node (ref "J62") (pin "4") (pinfunction "4_4") (pintype "bidirectional"))
      (node (ref "J63") (pin "4") (pinfunction "4_4") (pintype "bidirectional"))
      (node (ref "J64") (pin "4") (pinfunction "4_4") (pintype "bidirectional"))
      (node (ref "J7") (pin "4") (pinfunction "4_4") (pintype "bidirectional"))
      (node (ref "J8") (pin "4") (pinfunction "4_4") (pintype "bidirectional"))
      (node (ref "J9") (pin "4") (pinfunction "4_4") (pintype "bidirectional"))
      (node (ref "JP1") (pin "2") (pinfunction "2_2") (pintype "passive"))
      (node (ref "JP2") (pin "4") (pinfunction "4_4") (pintype "passive"))
      (node (ref "Q3") (pin "2") (pinfunction "S_2") (pintype "passive"))
      (node (ref "R10") (pin "1") (pinfunction "1_1") (pintype "bidirectional"))
      (node (ref "R12") (pin "1") (pinfunction "1_1") (pintype "bidirectional"))
      (node (ref "R5") (pin "2") (pinfunction "2_2") (pintype "bidirectional"))
      (node (ref "S1") (pin "3") (pinfunction "S_3") (pintype "passive"))
      (node (ref "SV1") (pin "4") (pinfunction "S_4") (pintype "passive"))
      (node (ref "U$1") (pin "GND") (pinfunction "GND_GND") (pintype "bidirectional"))
      (node (ref "U2") (pin "COM1") (pinfunction "COM1_COM1") (pintype "bidirectional"))
      (node (ref "U2") (pin "COM2") (pinfunction "COM2_COM2") (pintype "bidirectional"))
      (node (ref "U2") (pin "COM3") (pinfunction "COM3_COM3") (pintype "bidirectional"))
      (node (ref "U2") (pin "COM4") (pinfunction "COM4_COM4") (pintype "bidirectional"))
    )
    (net (code "17") (name "MICROPH") (class "Default")
      (node (ref "A1") (pin "D3") (pinfunction "D3_D3") (pintype "bidirectional"))
      (node (ref "JP1") (pin "11") (pinfunction "11_11") (pintype "passive"))
      (node (ref "R9") (pin "1") (pinfunction "1_1") (pintype "bidirectional"))
    )
    (net (code "18") (name "Net-(C6-Pad1)") (class "Default")
      (node (ref "C6") (pin "1") (pinfunction "1_1") (pintype "bidirectional"))
      (node (ref "R13") (pin "1") (pinfunction "1_1") (pintype "bidirectional"))
      (node (ref "U$1") (pin "IN") (pinfunction "IN_IN") (pintype "bidirectional"))
    )
    (net (code "19") (name "Net-(FDD6637-G)") (class "Default")
      (node (ref "FDD6637") (pin "1") (pinfunction "G_1") (pintype "passive"))
      (node (ref "R4") (pin "2") (pinfunction "2_2") (pintype "bidirectional"))
      (node (ref "R5") (pin "1") (pinfunction "1_1") (pintype "bidirectional"))
      (node (ref "U1") (pin "3") (pinfunction "C_3") (pintype "passive"))
    )
    (net (code "20") (name "Net-(FDD6637-S)") (class "Default")
      (node (ref "FDD6637") (pin "2") (pinfunction "S_2") (pintype "passive"))
      (node (ref "R3") (pin "2") (pinfunction "2_2") (pintype "bidirectional"))
      (node (ref "R4") (pin "1") (pinfunction "1_1") (pintype "bidirectional"))
      (node (ref "U1") (pin "1") (pinfunction "B_1") (pintype "passive"))
    )
    (net (code "21") (name "Net-(IC1-+IN)") (class "Default")
      (node (ref "IC1") (pin "1") (pinfunction "+IN_1") (pintype "input"))
      (node (ref "R8") (pin "2") (pinfunction "2_2") (pintype "bidirectional"))
    )
    (net (code "22") (name "Net-(IC1--IN)") (class "Default")
      (node (ref "IC1") (pin "3") (pinfunction "-IN_3") (pintype "input"))
      (node (ref "R10") (pin "2") (pinfunction "2_2") (pintype "bidirectional"))
      (node (ref "R7") (pin "1") (pinfunction "1_1") (pintype "bidirectional"))
    )
    (net (code "23") (name "Net-(IC1-OUT)") (class "Default")
      (node (ref "C7") (pin "1") (pinfunction "1_1") (pintype "bidirectional"))
      (node (ref "IC1") (pin "4") (pinfunction "OUT_4") (pintype "output"))
      (node (ref "R7") (pin "2") (pinfunction "2_2") (pintype "bidirectional"))
    )
    (net (code "24") (name "Net-(J1-Pad3)") (class "Default")
      (node (ref "J1") (pin "3") (pinfunction "3_3") (pintype "bidirectional"))
      (node (ref "J2") (pin "2") (pinfunction "2_2") (pintype "bidirectional"))
    )
    (net (code "25") (name "Net-(J2-Pad3)") (class "Default")
      (node (ref "J2") (pin "3") (pinfunction "3_3") (pintype "bidirectional"))
      (node (ref "J3") (pin "2") (pinfunction "2_2") (pintype "bidirectional"))
    )
    (net (code "26") (name "Net-(J3-Pad3)") (class "Default")
      (node (ref "J3") (pin "3") (pinfunction "3_3") (pintype "bidirectional"))
      (node (ref "J4") (pin "2") (pinfunction "2_2") (pintype "bidirectional"))
    )
    (net (code "27") (name "Net-(J4-Pad3)") (class "Default")
      (node (ref "J4") (pin "3") (pinfunction "3_3") (pintype "bidirectional"))
      (node (ref "J5") (pin "2") (pinfunction "2_2") (pintype "bidirectional"))
    )
    (net (code "28") (name "Net-(J5-Pad3)") (class "Default")
      (node (ref "J5") (pin "3") (pinfunction "3_3") (pintype "bidirectional"))
      (node (ref "J6") (pin "2") (pinfunction "2_2") (pintype "bidirectional"))
    )
    (net (code "29") (name "Net-(J6-Pad3)") (class "Default")
      (node (ref "J6") (pin "3") (pinfunction "3_3") (pintype "bidirectional"))
      (node (ref "J7") (pin "2") (pinfunction "2_2") (pintype "bidirectional"))
    )
    (net (code "30") (name "Net-(J7-Pad3)") (class "Default")
      (node (ref "J7") (pin "3") (pinfunction "3_3") (pintype "bidirectional"))
      (node (ref "J8") (pin "2") (pinfunction "2_2") (pintype "bidirectional"))
    )
    (net (code "31") (name "Net-(J8-Pad3)") (class "Default")
      (node (ref "J8") (pin "3") (pinfunction "3_3") (pintype "bidirectional"))
      (node (ref "J9") (pin "2") (pinfunction "2_2") (pintype "bidirectional"))
    )
    (net (code "32") (name "Net-(J10-Pad2)") (class "Default")
      (node (ref "J10") (pin "2") (pinfunction "2_2") (pintype "bidirectional"))
      (node (ref "J9") (pin "3") (pinfunction "3_3") (pintype "bidirectional"))
    )
    (net (code "33") (name "Net-(J10-Pad3)") (class "Default")
      (node (ref "J10") (pin "3") (pinfunction "3_3") (pintype "bidirectional"))
      (node (ref "J11") (pin "2") (pinfunction "2_2") (pintype "bidirectional"))
    )
    (net (code "34") (name "Net-(J11-Pad3)") (class "Default")
      (node (ref "J11") (pin "3") (pinfunction "3_3") (pintype "bidirectional"))
      (node (ref "J12") (pin "2") (pinfunction "2_2") (pintype "bidirectional"))
    )
    (net (code "35") (name "Net-(J12-Pad3)") (class "Default")
      (node (ref "J12") (pin "3") (pinfunction "3_3") (pintype "bidirectional"))
      (node (ref "J13") (pin "2") (pinfunction "2_2") (pintype "bidirectional"))
    )
    (net (code "36") (name "Net-(J13-Pad3)") (class "Default")
      (node (ref "J13") (pin "3") (pinfunction "3_3") (pintype "bidirectional"))
      (node (ref "J14") (pin "2") (pinfunction "2_2") (pintype "bidirectional"))
    )
    (net (code "37") (name "Net-(J14-Pad3)") (class "Default")
      (node (ref "J14") (pin "3") (pinfunction "3_3") (pintype "bidirectional"))
      (node (ref "J15") (pin "2") (pinfunction "2_2") (pintype "bidirectional"))
    )
    (net (code "38") (name "Net-(J15-Pad3)") (class "Default")
      (node (ref "J15") (pin "3") (pinfunction "3_3") (pintype "bidirectional"))
      (node (ref "J16") (pin "2") (pinfunction "2_2") (pintype "bidirectional"))
    )
    (net (code "39") (name "Net-(J16-Pad3)") (class "Default")
      (node (ref "J16") (pin "3") (pinfunction "3_3") (pintype "bidirectional"))
      (node (ref "J17") (pin "2") (pinfunction "2_2") (pintype "bidirectional"))
    )
    (net (code "40") (name "Net-(J17-Pad3)") (class "Default")
      (node (ref "J17") (pin "3") (pinfunction "3_3") (pintype "bidirectional"))
      (node (ref "J18") (pin "2") (pinfunction "2_2") (pintype "bidirectional"))
    )
    (net (code "41") (name "Net-(J18-Pad3)") (class "Default")
      (node (ref "J18") (pin "3") (pinfunction "3_3") (pintype "bidirectional"))
      (node (ref "J19") (pin "2") (pinfunction "2_2") (pintype "bidirectional"))
    )
    (net (code "42") (name "Net-(J19-Pad3)") (class "Default")
      (node (ref "J19") (pin "3") (pinfunction "3_3") (pintype "bidirectional"))
      (node (ref "J20") (pin "2") (pinfunction "2_2") (pintype "bidirectional"))
    )
    (net (code "43") (name "Net-(J20-Pad3)") (class "Default")
      (node (ref "J20") (pin "3") (pinfunction "3_3") (pintype "bidirectional"))
      (node (ref "J21") (pin "2") (pinfunction "2_2") (pintype "bidirectional"))
    )
    (net (code "44") (name "Net-(J21-Pad3)") (class "Default")
      (node (ref "J21") (pin "3") (pinfunction "3_3") (pintype "bidirectional"))
      (node (ref "J22") (pin "2") (pinfunction "2_2") (pintype "bidirectional"))
    )
    (net (code "45") (name "Net-(J22-Pad3)") (class "Default")
      (node (ref "J22") (pin "3") (pinfunction "3_3") (pintype "bidirectional"))
      (node (ref "J23") (pin "2") (pinfunction "2_2") (pintype "bidirectional"))
    )
    (net (code "46") (name "Net-(J23-Pad3)") (class "Default")
      (node (ref "J23") (pin "3") (pinfunction "3_3") (pintype "bidirectional"))
      (node (ref "J24") (pin "2") (pinfunction "2_2") (pintype "bidirectional"))
    )
    (net (code "47") (name "Net-(J24-Pad3)") (class "Default")
      (node (ref "J24") (pin "3") (pinfunction "3_3") (pintype "bidirectional"))
      (node (ref "J25") (pin "2") (pinfunction "2_2") (pintype "bidirectional"))
    )
    (net (code "48") (name "Net-(J25-Pad3)") (class "Default")
      (node (ref "J25") (pin "3") (pinfunction "3_3") (pintype "bidirectional"))
      (node (ref "J26") (pin "2") (pinfunction "2_2") (pintype "bidirectional"))
    )
    (net (code "49") (name "Net-(J26-Pad3)") (class "Default")
      (node (ref "J26") (pin "3") (pinfunction "3_3") (pintype "bidirectional"))
      (node (ref "J27") (pin "2") (pinfunction "2_2") (pintype "bidirectional"))
    )
    (net (code "50") (name "Net-(J27-Pad3)") (class "Default")
      (node (ref "J27") (pin "3") (pinfunction "3_3") (pintype "bidirectional"))
      (node (ref "J28") (pin "2") (pinfunction "2_2") (pintype "bidirectional"))
    )
    (net (code "51") (name "Net-(J28-Pad3)") (class "Default")
      (node (ref "J28") (pin "3") (pinfunction "3_3") (pintype "bidirectional"))
      (node (ref "J29") (pin "2") (pinfunction "2_2") (pintype "bidirectional"))
    )
    (net (code "52") (name "Net-(J29-Pad3)") (class "Default")
      (node (ref "J29") (pin "3") (pinfunction "3_3") (pintype "bidirectional"))
      (node (ref "J30") (pin "2") (pinfunction "2_2") (pintype "bidirectional"))
    )
    (net (code "53") (name "Net-(J30-Pad3)") (class "Default")
      (node (ref "J30") (pin "3") (pinfunction "3_3") (pintype "bidirectional"))
      (node (ref "J31") (pin "2") (pinfunction "2_2") (pintype "bidirectional"))
    )
    (net (code "54") (name "Net-(J31-Pad3)") (class "Default")
      (node (ref "J31") (pin "3") (pinfunction "3_3") (pintype "bidirectional"))
      (node (ref "J32") (pin "2") (pinfunction "2_2") (pintype "bidirectional"))
    )
    (net (code "55") (name "Net-(J32-Pad3)") (class "Default")
      (node (ref "J32") (pin "3") (pinfunction "3_3") (pintype "bidirectional"))
      (node (ref "J33") (pin "2") (pinfunction "2_2") (pintype "bidirectional"))
    )
    (net (code "56") (name "Net-(J33-Pad3)") (class "Default")
      (node (ref "J33") (pin "3") (pinfunction "3_3") (pintype "bidirectional"))
      (node (ref "J34") (pin "2") (pinfunction "2_2") (pintype "bidirectional"))
    )
    (net (code "57") (name "Net-(J34-Pad3)") (class "Default")
      (node (ref "J34") (pin "3") (pinfunction "3_3") (pintype "bidirectional"))
      (node (ref "J35") (pin "2") (pinfunction "2_2") (pintype "bidirectional"))
    )
    (net (code "58") (name "Net-(J35-Pad3)") (class "Default")
      (node (ref "J35") (pin "3") (pinfunction "3_3") (pintype "bidirectional"))
      (node (ref "J36") (pin "2") (pinfunction "2_2") (pintype "bidirectional"))
    )
    (net (code "59") (name "Net-(J36-Pad3)") (class "Default")
      (node (ref "J36") (pin "3") (pinfunction "3_3") (pintype "bidirectional"))
      (node (ref "J37") (pin "2") (pinfunction "2_2") (pintype "bidirectional"))
    )
    (net (code "60") (name "Net-(J37-Pad3)") (class "Default")
      (node (ref "J37") (pin "3") (pinfunction "3_3") (pintype "bidirectional"))
      (node (ref "J38") (pin "2") (pinfunction "2_2") (pintype "bidirectional"))
    )
    (net (code "61") (name "Net-(J38-Pad3)") (class "Default")
      (node (ref "J38") (pin "3") (pinfunction "3_3") (pintype "bidirectional"))
      (node (ref "J39") (pin "2") (pinfunction "2_2") (pintype "bidirectional"))
    )
    (net (code "62") (name "Net-(J39-Pad3)") (class "Default")
      (node (ref "J39") (pin "3") (pinfunction "3_3") (pintype "bidirectional"))
      (node (ref "J40") (pin "2") (pinfunction "2_2") (pintype "bidirectional"))
    )
    (net (code "63") (name "Net-(J40-Pad3)") (class "Default")
      (node (ref "J40") (pin "3") (pinfunction "3_3") (pintype "bidirectional"))
      (node (ref "J41") (pin "2") (pinfunction "2_2") (pintype "bidirectional"))
    )
    (net (code "64") (name "Net-(J41-Pad3)") (class "Default")
      (node (ref "J41") (pin "3") (pinfunction "3_3") (pintype "bidirectional"))
      (node (ref "J42") (pin "2") (pinfunction "2_2") (pintype "bidirectional"))
    )
    (net (code "65") (name "Net-(J42-Pad3)") (class "Default")
      (node (ref "J42") (pin "3") (pinfunction "3_3") (pintype "bidirectional"))
      (node (ref "J43") (pin "2") (pinfunction "2_2") (pintype "bidirectional"))
    )
    (net (code "66") (name "Net-(J43-Pad3)") (class "Default")
      (node (ref "J43") (pin "3") (pinfunction "3_3") (pintype "bidirectional"))
      (node (ref "J44") (pin "2") (pinfunction "2_2") (pintype "bidirectional"))
    )
    (net (code "67") (name "Net-(J44-Pad3)") (class "Default")
      (node (ref "J44") (pin "3") (pinfunction "3_3") (pintype "bidirectional"))
      (node (ref "J45") (pin "2") (pinfunction "2_2") (pintype "bidirectional"))
    )
    (net (code "68") (name "Net-(J45-Pad3)") (class "Default")
      (node (ref "J45") (pin "3") (pinfunction "3_3") (pintype "bidirectional"))
      (node (ref "J46") (pin "2") (pinfunction "2_2") (pintype "bidirectional"))
    )
    (net (code "69") (name "Net-(J46-Pad3)") (class "Default")
      (node (ref "J46") (pin "3") (pinfunction "3_3") (pintype "bidirectional"))
      (node (ref "J47") (pin "2") (pinfunction "2_2") (pintype "bidirectional"))
    )
    (net (code "70") (name "Net-(J47-Pad3)") (class "Default")
      (node (ref "J47") (pin "3") (pinfunction "3_3") (pintype "bidirectional"))
      (node (ref "J48") (pin "2") (pinfunction "2_2") (pintype "bidirectional"))
    )
    (net (code "71") (name "Net-(J48-Pad3)") (class "Default")
      (node (ref "J48") (pin "3") (pinfunction "3_3") (pintype "bidirectional"))
      (node (ref "J49") (pin "2") (pinfunction "2_2") (pintype "bidirectional"))
    )
    (net (code "72") (name "Net-(J49-Pad3)") (class "Default")
      (node (ref "J49") (pin "3") (pinfunction "3_3") (pintype "bidirectional"))
      (node (ref "J50") (pin "2") (pinfunction "2_2") (pintype "bidirectional"))
    )
    (net (code "73") (name "Net-(J50-Pad3)") (class "Default")
      (node (ref "J50") (pin "3") (pinfunction "3_3") (pintype "bidirectional"))
      (node (ref "J51") (pin "2") (pinfunction "2_2") (pintype "bidirectional"))
    )
    (net (code "74") (name "Net-(J51-Pad3)") (class "Default")
      (node (ref "J51") (pin "3") (pinfunction "3_3") (pintype "bidirectional"))
      (node (ref "J52") (pin "2") (pinfunction "2_2") (pintype "bidirectional"))
    )
    (net (code "75") (name "Net-(J52-Pad3)") (class "Default")
      (node (ref "J52") (pin "3") (pinfunction "3_3") (pintype "bidirectional"))
      (node (ref "J53") (pin "2") (pinfunction "2_2") (pintype "bidirectional"))
    )
    (net (code "76") (name "Net-(J53-Pad3)") (class "Default")
      (node (ref "J53") (pin "3") (pinfunction "3_3") (pintype "bidirectional"))
      (node (ref "J54") (pin "2") (pinfunction "2_2") (pintype "bidirectional"))
    )
    (net (code "77") (name "Net-(J54-Pad3)") (class "Default")
      (node (ref "J54") (pin "3") (pinfunction "3_3") (pintype "bidirectional"))
      (node (ref "J55") (pin "2") (pinfunction "2_2") (pintype "bidirectional"))
    )
    (net (code "78") (name "Net-(J55-Pad3)") (class "Default")
      (node (ref "J55") (pin "3") (pinfunction "3_3") (pintype "bidirectional"))
      (node (ref "J56") (pin "2") (pinfunction "2_2") (pintype "bidirectional"))
    )
    (net (code "79") (name "Net-(J56-Pad3)") (class "Default")
      (node (ref "J56") (pin "3") (pinfunction "3_3") (pintype "bidirectional"))
      (node (ref "J57") (pin "2") (pinfunction "2_2") (pintype "bidirectional"))
    )
    (net (code "80") (name "Net-(J57-Pad3)") (class "Default")
      (node (ref "J57") (pin "3") (pinfunction "3_3") (pintype "bidirectional"))
      (node (ref "J58") (pin "2") (pinfunction "2_2") (pintype "bidirectional"))
    )
    (net (code "81") (name "Net-(J58-Pad3)") (class "Default")
      (node (ref "J58") (pin "3") (pinfunction "3_3") (pintype "bidirectional"))
      (node (ref "J59") (pin "2") (pinfunction "2_2") (pintype "bidirectional"))
    )
    (net (code "82") (name "Net-(J59-Pad3)") (class "Default")
      (node (ref "J59") (pin "3") (pinfunction "3_3") (pintype "bidirectional"))
      (node (ref "J60") (pin "2") (pinfunction "2_2") (pintype "bidirectional"))
    )
    (net (code "83") (name "Net-(J60-Pad3)") (class "Default")
      (node (ref "J60") (pin "3") (pinfunction "3_3") (pintype "bidirectional"))
      (node (ref "J61") (pin "2") (pinfunction "2_2") (pintype "bidirectional"))
    )
    (net (code "84") (name "Net-(J61-Pad3)") (class "Default")
      (node (ref "J61") (pin "3") (pinfunction "3_3") (pintype "bidirectional"))
      (node (ref "J62") (pin "2") (pinfunction "2_2") (pintype "bidirectional"))
    )
    (net (code "85") (name "Net-(J62-Pad3)") (class "Default")
      (node (ref "J62") (pin "3") (pinfunction "3_3") (pintype "bidirectional"))
      (node (ref "J63") (pin "2") (pinfunction "2_2") (pintype "bidirectional"))
    )
    (net (code "86") (name "Net-(J63-Pad3)") (class "Default")
      (node (ref "J63") (pin "3") (pinfunction "3_3") (pintype "bidirectional"))
      (node (ref "J64") (pin "2") (pinfunction "2_2") (pintype "bidirectional"))
    )
    (net (code "87") (name "Net-(Q3-D)") (class "Default")
      (node (ref "C6") (pin "2") (pinfunction "2_2") (pintype "bidirectional"))
      (node (ref "Q3") (pin "3") (pinfunction "D_3") (pintype "passive"))
      (node (ref "R8") (pin "1") (pinfunction "1_1") (pintype "bidirectional"))
    )
    (net (code "88") (name "Net-(Q3-G)") (class "Default")
      (node (ref "C5") (pin "1") (pinfunction "1_1") (pintype "bidirectional"))
      (node (ref "Q3") (pin "1") (pinfunction "G_1") (pintype "passive"))
      (node (ref "R9") (pin "2") (pinfunction "2_2") (pintype "bidirectional"))
    )
    (net (code "89") (name "SOUND") (class "Default")
      (node (ref "A1") (pin "A0") (pinfunction "A0_A0") (pintype "bidirectional"))
      (node (ref "C7") (pin "2") (pinfunction "2_2") (pintype "bidirectional"))
      (node (ref "JP1") (pin "10") (pinfunction "10_10") (pintype "passive"))
      (node (ref "R11") (pin "1") (pinfunction "1_1") (pintype "bidirectional"))
      (node (ref "R12") (pin "2") (pinfunction "2_2") (pintype "bidirectional"))
    )
    (net (code "90") (name "SWITCH") (class "Default")
      (node (ref "A1") (pin "D4") (pinfunction "D4_D4") (pintype "bidirectional"))
      (node (ref "JP2") (pin "10") (pinfunction "10_10") (pintype "passive"))
      (node (ref "R6") (pin "2") (pinfunction "2_2") (pintype "bidirectional"))
      (node (ref "S1") (pin "2") (pinfunction "P_2") (pintype "passive"))
    )
    (net (code "91") (name "V+") (class "Default")
      (node (ref "A1") (pin "A4") (pinfunction "A4_A4") (pintype "bidirectional"))
      (node (ref "C1") (pin "+") (pinfunction "1_+") (pintype "bidirectional"))
      (node (ref "C2") (pin "+") (pinfunction "1_+") (pintype "bidirectional"))
      (node (ref "C3") (pin "2") (pinfunction "2_2") (pintype "bidirectional"))
      (node (ref "FDD6637") (pin "3") (pinfunction "D_3") (pintype "passive"))
      (node (ref "J1") (pin "1") (pinfunction "1_1") (pintype "bidirectional"))
      (node (ref "J10") (pin "1") (pinfunction "1_1") (pintype "bidirectional"))
      (node (ref "J11") (pin "1") (pinfunction "1_1") (pintype "bidirectional"))
      (node (ref "J12") (pin "1") (pinfunction "1_1") (pintype "bidirectional"))
      (node (ref "J13") (pin "1") (pinfunction "1_1") (pintype "bidirectional"))
      (node (ref "J14") (pin "1") (pinfunction "1_1") (pintype "bidirectional"))
      (node (ref "J15") (pin "1") (pinfunction "1_1") (pintype "bidirectional"))
      (node (ref "J16") (pin "1") (pinfunction "1_1") (pintype "bidirectional"))
      (node (ref "J17") (pin "1") (pinfunction "1_1") (pintype "bidirectional"))
      (node (ref "J18") (pin "1") (pinfunction "1_1") (pintype "bidirectional"))
      (node (ref "J19") (pin "1") (pinfunction "1_1") (pintype "bidirectional"))
      (node (ref "J2") (pin "1") (pinfunction "1_1") (pintype "bidirectional"))
      (node (ref "J20") (pin "1") (pinfunction "1_1") (pintype "bidirectional"))
      (node (ref "J21") (pin "1") (pinfunction "1_1") (pintype "bidirectional"))
      (node (ref "J22") (pin "1") (pinfunction "1_1") (pintype "bidirectional"))
      (node (ref "J23") (pin "1") (pinfunction "1_1") (pintype "bidirectional"))
      (node (ref "J24") (pin "1") (pinfunction "1_1") (pintype "bidirectional"))
      (node (ref "J25") (pin "1") (pinfunction "1_1") (pintype "bidirectional"))
      (node (ref "J26") (pin "1") (pinfunction "1_1") (pintype "bidirectional"))
      (node (ref "J27") (pin "1") (pinfunction "1_1") (pintype "bidirectional"))
      (node (ref "J28") (pin "1") (pinfunction "1_1") (pintype "bidirectional"))
      (node (ref "J29") (pin "1") (pinfunction "1_1") (pintype "bidirectional"))
      (node (ref "J3") (pin "1") (pinfunction "1_1") (pintype "bidirectional"))
      (node (ref "J30") (pin "1") (pinfunction "1_1") (pintype "bidirectional"))
      (node (ref "J31") (pin "1") (pinfunction "1_1") (pintype "bidirectional"))
      (node (ref "J32") (pin "1") (pinfunction "1_1") (pintype "bidirectional"))
      (node (ref "J33") (pin "1") (pinfunction "1_1") (pintype "bidirectional"))
      (node (ref "J34") (pin "1") (pinfunction "1_1") (pintype "bidirectional"))
      (node (ref "J35") (pin "1") (pinfunction "1_1") (pintype "bidirectional"))
      (node (ref "J36") (pin "1") (pinfunction "1_1") (pintype "bidirectional"))
      (node (ref "J37") (pin "1") (pinfunction "1_1") (pintype "bidirectional"))
      (node (ref "J38") (pin "1") (pinfunction "1_1") (pintype "bidirectional"))
      (node (ref "J39") (pin "1") (pinfunction "1_1") (pintype "bidirectional"))
      (node (ref "J4") (pin "1") (pinfunction "1_1") (pintype "bidirectional"))
      (node (ref "J40") (pin "1") (pinfunction "1_1") (pintype "bidirectional"))
      (node (ref "J41") (pin "1") (pinfunction "1_1") (pintype "bidirectional"))
      (node (ref "J42") (pin "1") (pinfunction "1_1") (pintype "bidirectional"))
      (node (ref "J43") (pin "1") (pinfunction "1_1") (pintype "bidirectional"))
      (node (ref "J44") (pin "1") (pinfunction "1_1") (pintype "bidirectional"))
      (node (ref "J45") (pin "1") (pinfunction "1_1") (pintype "bidirectional"))
      (node (ref "J46") (pin "1") (pinfunction "1_1") (pintype "bidirectional"))
      (node (ref "J47") (pin "1") (pinfunction "1_1") (pintype "bidirectional"))
      (node (ref "J48") (pin "1") (pinfunction "1_1") (pintype "bidirectional"))
      (node (ref "J49") (pin "1") (pinfunction "1_1") (pintype "bidirectional"))
      (node (ref "J5") (pin "1") (pinfunction "1_1") (pintype "bidirectional"))
      (node (ref "J50") (pin "1") (pinfunction "1_1") (pintype "bidirectional"))
      (node (ref "J51") (pin "1") (pinfunction "1_1") (pintype "bidirectional"))
      (node (ref "J52") (pin "1") (pinfunction "1_1") (pintype "bidirectional"))
      (node (ref "J53") (pin "1") (pinfunction "1_1") (pintype "bidirectional"))
      (node (ref "J54") (pin "1") (pinfunction "1_1") (pintype "bidirectional"))
      (node (ref "J55") (pin "1") (pinfunction "1_1") (pintype "bidirectional"))
      (node (ref "J56") (pin "1") (pinfunction "1_1") (pintype "bidirectional"))
      (node (ref "J57") (pin "1") (pinfunction "1_1") (pintype "bidirectional"))
      (node (ref "J58") (pin "1") (pinfunction "1_1") (pintype "bidirectional"))
      (node (ref "J59") (pin "1") (pinfunction "1_1") (pintype "bidirectional"))
      (node (ref "J6") (pin "1") (pinfunction "1_1") (pintype "bidirectional"))
      (node (ref "J60") (pin "1") (pinfunction "1_1") (pintype "bidirectional"))
      (node (ref "J61") (pin "1") (pinfunction "1_1") (pintype "bidirectional"))
      (node (ref "J62") (pin "1") (pinfunction "1_1") (pintype "bidirectional"))
      (node (ref "J63") (pin "1") (pinfunction "1_1") (pintype "bidirectional"))
      (node (ref "J64") (pin "1") (pinfunction "1_1") (pintype "bidirectional"))
      (node (ref "J7") (pin "1") (pinfunction "1_1") (pintype "bidirectional"))
      (node (ref "J8") (pin "1") (pinfunction "1_1") (pintype "bidirectional"))
      (node (ref "J9") (pin "1") (pinfunction "1_1") (pintype "bidirectional"))
      (node (ref "JP1") (pin "6") (pinfunction "6_6") (pintype "passive"))
    )
    (net (code "92") (name "XOUT") (class "Default")
      (node (ref "A1") (pin "A1") (pinfunction "A1_A1") (pintype "bidirectional"))
      (node (ref "C11") (pin "2") (pinfunction "2_2") (pintype "bidirectional"))
      (node (ref "JP1") (pin "9") (pinfunction "9_9") (pintype "passive"))
      (node (ref "U2") (pin "X") (pinfunction "X_X") (pintype "bidirectional"))
    )
    (net (code "93") (name "YOUT") (class "Default")
      (node (ref "A1") (pin "A2") (pinfunction "A2_A2") (pintype "bidirectional"))
      (node (ref "C10") (pin "2") (pinfunction "2_2") (pintype "bidirectional"))
      (node (ref "JP1") (pin "8") (pinfunction "8_8") (pintype "passive"))
      (node (ref "U2") (pin "Y") (pinfunction "Y_Y") (pintype "bidirectional"))
    )
    (net (code "94") (name "ZOUT") (class "Default")
      (node (ref "A1") (pin "A3") (pinfunction "A3_A3") (pintype "bidirectional"))
      (node (ref "C9") (pin "2") (pinfunction "2_2") (pintype "bidirectional"))
      (node (ref "JP1") (pin "7") (pinfunction "7_7") (pintype "passive"))
      (node (ref "U2") (pin "Z") (pinfunction "Z_Z") (pintype "bidirectional"))
    )
    (net (code "95") (name "unconnected-(A1-1-Pad100)") (class "Default")
      (node (ref "A1") (pin "100") (pinfunction "1_100") (pintype "bidirectional"))
    )
    (net (code "96") (name "unconnected-(A1-PadA5)") (class "Default")
      (node (ref "A1") (pin "A5") (pinfunction "A5_A5") (pintype "bidirectional"))
    )
    (net (code "97") (name "unconnected-(A1-PadD0)") (class "Default")
      (node (ref "A1") (pin "D0") (pinfunction "D0_D0") (pintype "bidirectional"))
    )
    (net (code "98") (name "unconnected-(A1-PadD1)") (class "Default")
      (node (ref "A1") (pin "D1") (pinfunction "D1_D1") (pintype "bidirectional"))
    )
    (net (code "99") (name "unconnected-(A1-PadD5)") (class "Default")
      (node (ref "A1") (pin "D5") (pinfunction "D5_D5") (pintype "bidirectional"))
    )
    (net (code "100") (name "unconnected-(A1-PadD6)") (class "Default")
      (node (ref "A1") (pin "D6") (pinfunction "D6_D6") (pintype "bidirectional"))
    )
    (net (code "101") (name "unconnected-(A1-PadD7)") (class "Default")
      (node (ref "A1") (pin "D7") (pinfunction "D7_D7") (pintype "bidirectional"))
    )
    (net (code "102") (name "unconnected-(A1-PadD8)") (class "Default")
      (node (ref "A1") (pin "D8") (pinfunction "D8_D8") (pintype "bidirectional"))
    )
    (net (code "103") (name "unconnected-(A1-PadD9)") (class "Default")
      (node (ref "A1") (pin "D9") (pinfunction "D9_D9") (pintype "bidirectional"))
    )
    (net (code "104") (name "unconnected-(A1-PadD10)") (class "Default")
      (node (ref "A1") (pin "D10") (pinfunction "D10_D10") (pintype "bidirectional"))
    )
    (net (code "105") (name "unconnected-(A1-PadD11)") (class "Default")
      (node (ref "A1") (pin "D11") (pinfunction "D11_D11") (pintype "bidirectional"))
    )
    (net (code "106") (name "unconnected-(A1-PadD12)") (class "Default")
      (node (ref "A1") (pin "D12") (pinfunction "D12_D12") (pintype "bidirectional"))
    )
    (net (code "107") (name "unconnected-(A1-PadD13)") (class "Default")
      (node (ref "A1") (pin "D13") (pinfunction "D13_D13") (pintype "bidirectional"))
    )
    (net (code "108") (name "unconnected-(A1-PadIOREF)") (class "Default")
      (node (ref "A1") (pin "IOREF") (pinfunction "IOREF_IOREF") (pintype "bidirectional"))
    )
    (net (code "109") (name "unconnected-(A1-PadRESET)") (class "Default")
      (node (ref "A1") (pin "RESET") (pinfunction "RESET_RESET") (pintype "bidirectional"))
    )
    (net (code "110") (name "unconnected-(A1-PadVIN)") (class "Default")
      (node (ref "A1") (pin "VIN") (pinfunction "VIN_VIN") (pintype "bidirectional"))
    )
    (net (code "111") (name "unconnected-(J64-Pad3)") (class "Default")
      (node (ref "J64") (pin "3") (pinfunction "3_3") (pintype "bidirectional"))
    )
    (net (code "112") (name "unconnected-(S1-O-Pad1)") (class "Default")
      (node (ref "S1") (pin "1") (pinfunction "O_1") (pintype "passive"))
    )
    (net (code "113") (name "unconnected-(SV1C-S-Pad3)") (class "Default")
      (node (ref "SV1") (pin "3") (pinfunction "S_3") (pintype "passive"))
    )
    (net (code "114") (name "unconnected-(U2-PadNC1)") (class "Default")
      (node (ref "U2") (pin "NC1") (pinfunction "NC1_NC1") (pintype "bidirectional"))
    )
    (net (code "115") (name "unconnected-(U2-PadNC2)") (class "Default")
      (node (ref "U2") (pin "NC2") (pinfunction "NC2_NC2") (pintype "bidirectional"))
    )
    (net (code "116") (name "unconnected-(U2-PadNC3)") (class "Default")
      (node (ref "U2") (pin "NC3") (pinfunction "NC3_NC3") (pintype "bidirectional"))
    )
    (net (code "117") (name "unconnected-(U2-PadNC4)") (class "Default")
      (node (ref "U2") (pin "NC4") (pinfunction "NC4_NC4") (pintype "bidirectional"))
    )
    (net (code "118") (name "unconnected-(U2-PadNC5)") (class "Default")
      (node (ref "U2") (pin "NC5") (pinfunction "NC5_NC5") (pintype "bidirectional"))
    )
    (net (code "119") (name "unconnected-(U2-PadNC6)") (class "Default")
      (node (ref "U2") (pin "NC6") (pinfunction "NC6_NC6") (pintype "bidirectional"))
    )
    (net (code "120") (name "unconnected-(U2-PadST)") (class "Default")
      (node (ref "U2") (pin "ST") (pinfunction "ST_ST") (pintype "bidirectional"))
    )
  )
)
